# Triangle_Generator.net
KiCad netlist of a schematic drawn in Altium Designer
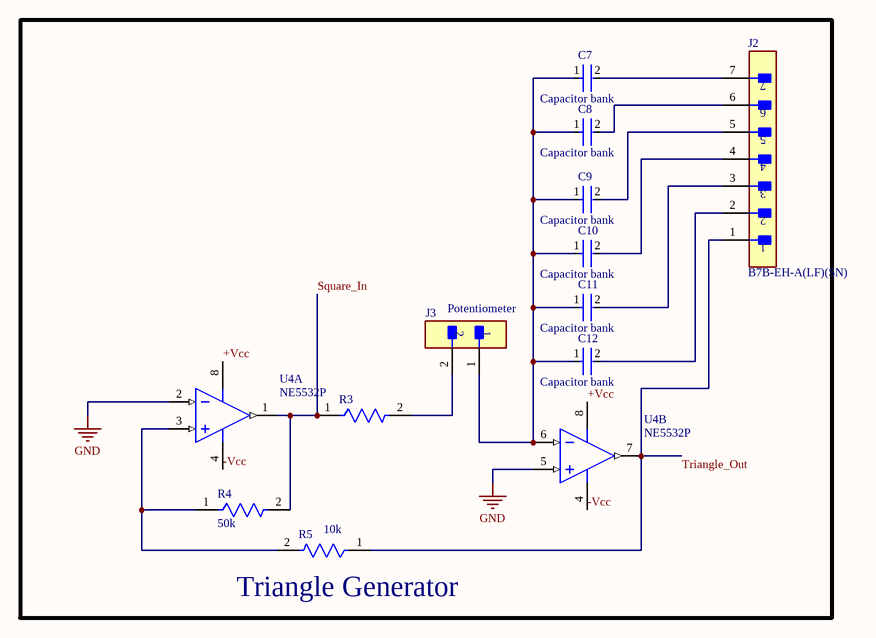
[diagram p0: Triangle_Generator.SchDoc]

(export (version "E")
  (design (tool "Eeschema 10.0.6"))
  (components
    (comp (ref "C7")
      (value "Capacitor bank")
      (footprint "FP-F471K33Y5RP6UK5R-MFG")
      (description "CAP CER 470PF 2KV Y5R RADIAL")
      (fields (field (name "TOLERANCE") "10%") (field (name "VOLTAGE") "2kV"))
      (libsource (lib "Altium Content Vault") (part "b4654b650e69147ec39a6b967a45e02"))
    )
    (comp (ref "C8")
      (value "Capacitor bank")
      (footprint "FP-F471K33Y5RP6UK5R-MFG")
      (description "CAP CER 470PF 2KV Y5R RADIAL")
      (fields (field (name "TOLERANCE") "10%") (field (name "VOLTAGE") "2kV"))
      (libsource (lib "Altium Content Vault") (part "b4654b650e69147ec39a6b967a45e02"))
    )
    (comp (ref "C9")
      (value "Capacitor bank")
      (footprint "FP-F471K33Y5RP6UK5R-MFG")
      (description "CAP CER 470PF 2KV Y5R RADIAL")
      (fields (field (name "TOLERANCE") "10%") (field (name "VOLTAGE") "2kV"))
      (libsource (lib "Altium Content Vault") (part "b4654b650e69147ec39a6b967a45e02"))
    )
    (comp (ref "C10")
      (value "Capacitor bank")
      (footprint "FP-F471K33Y5RP6UK5R-MFG")
      (description "CAP CER 470PF 2KV Y5R RADIAL")
      (fields (field (name "TOLERANCE") "10%") (field (name "VOLTAGE") "2kV"))
      (libsource (lib "Altium Content Vault") (part "b4654b650e69147ec39a6b967a45e02"))
    )
    (comp (ref "C11")
      (value "Capacitor bank")
      (footprint "FP-F471K33Y5RP6UK5R-MFG")
      (description "CAP CER 470PF 2KV Y5R RADIAL")
      (fields (field (name "TOLERANCE") "10%") (field (name "VOLTAGE") "2kV"))
      (libsource (lib "Altium Content Vault") (part "b4654b650e69147ec39a6b967a45e02"))
    )
    (comp (ref "C12")
      (value "Capacitor bank")
      (footprint "FP-F471K33Y5RP6UK5R-MFG")
      (description "CAP CER 470PF 2KV Y5R RADIAL")
      (fields (field (name "TOLERANCE") "10%") (field (name "VOLTAGE") "2kV"))
      (libsource (lib "Altium Content Vault") (part "b4654b650e69147ec39a6b967a45e02"))
    )
    (comp (ref "J2")
      (value "B7B-EH-A(LF)(SN)")
      (footprint "FP-B7B-EH-A_LF_SN-MFG")
      (description "CONN HEADER VERT 7POS 2.5MM")
      (libsource (lib "Altium Content Vault") (part "5bcee6b94e1fee4be3f4cc3a650a442"))
    )
    (comp (ref "J3")
      (value "Potentiometer")
      (footprint "FP-B2B-XH-A_LF_SN-MFG")
      (description "CONN HEADER VERT 2POS 2.5MM")
      (libsource (lib "Altium Content Vault") (part "3bc925449376181038e59eaffc5286c"))
    )
    (comp (ref "R3")
      (value "~")
      (footprint "FP-VR37-MFG")
      (description "RES 1.2M OHM 5% 1/2W AXIAL")
      (fields (field (name "TOLERANCE") "5%"))
      (libsource (lib "Altium Content Vault") (part "1029c3af85768c4190bb7ad29bc67b5"))
    )
    (comp (ref "R4")
      (value "50k")
      (footprint "FP-VR37-MFG")
      (description "RES 1.2M OHM 5% 1/2W AXIAL")
      (fields (field (name "TOLERANCE") "5%"))
      (libsource (lib "Altium Content Vault") (part "1029c3af85768c4190bb7ad29bc67b5"))
    )
    (comp (ref "R5")
      (value "10k")
      (footprint "FP-VR37-MFG")
      (description "RES 1.2M OHM 5% 1/2W AXIAL")
      (fields (field (name "TOLERANCE") "5%"))
      (libsource (lib "Altium Content Vault") (part "1029c3af85768c4190bb7ad29bc67b5"))
    )
    (comp (ref "U4")
      (value "NE5532P")
      (footprint "P0008A")
      (fields (field (name "MANUFACTURER") "Texas Instruments"))
      (libsource (lib "Altium Content Vault") (part "TI-AMP-D6-2-8_D"))
    )
  )
  (nets
    (net (code "1") (name "/+Vcc") (class "Default")
      (node (ref "U4") (pin "8") (pinfunction "VCC+_8") (pintype "power_in"))
    )
    (net (code "2") (name "/-Vcc") (class "Default")
      (node (ref "U4") (pin "4") (pinfunction "VCC-_4") (pintype "power_in"))
    )
    (net (code "3") (name "/Square_In") (class "Default")
      (node (ref "R3") (pin "1") (pinfunction "1_1") (pintype "passive"))
      (node (ref "R4") (pin "2") (pinfunction "2_2") (pintype "passive"))
      (node (ref "U4") (pin "1") (pinfunction "OUT1_1") (pintype "output"))
    )
    (net (code "4") (name "/Triangle_Out") (class "Default")
      (node (ref "J2") (pin "1") (pinfunction "1_1") (pintype "passive"))
      (node (ref "R5") (pin "1") (pinfunction "1_1") (pintype "passive"))
      (node (ref "U4") (pin "7") (pinfunction "OUT2_7") (pintype "output"))
    )
    (net (code "5") (name "GND") (class "Default")
      (node (ref "U4") (pin "2") (pinfunction "IN1-_2") (pintype "input"))
      (node (ref "U4") (pin "5") (pinfunction "IN2+_5") (pintype "input"))
    )
    (net (code "6") (name "Net-(C7-Pad2)") (class "Default")
      (node (ref "C7") (pin "2") (pinfunction "2_2") (pintype "passive"))
      (node (ref "J2") (pin "7") (pinfunction "7_7") (pintype "passive"))
    )
    (net (code "7") (name "Net-(C8-Pad2)") (class "Default")
      (node (ref "C8") (pin "2") (pinfunction "2_2") (pintype "passive"))
      (node (ref "J2") (pin "6") (pinfunction "6_6") (pintype "passive"))
    )
    (net (code "8") (name "Net-(C9-Pad2)") (class "Default")
      (node (ref "C9") (pin "2") (pinfunction "2_2") (pintype "passive"))
      (node (ref "J2") (pin "5") (pinfunction "5_5") (pintype "passive"))
    )
    (net (code "9") (name "Net-(C10-Pad2)") (class "Default")
      (node (ref "C10") (pin "2") (pinfunction "2_2") (pintype "passive"))
      (node (ref "J2") (pin "4") (pinfunction "4_4") (pintype "passive"))
    )
    (net (code "10") (name "Net-(C11-Pad2)") (class "Default")
      (node (ref "C11") (pin "2") (pinfunction "2_2") (pintype "passive"))
      (node (ref "J2") (pin "3") (pinfunction "3_3") (pintype "passive"))
    )
    (net (code "11") (name "Net-(C12-Pad2)") (class "Default")
      (node (ref "C12") (pin "2") (pinfunction "2_2") (pintype "passive"))
      (node (ref "J2") (pin "2") (pinfunction "2_2") (pintype "passive"))
    )
    (net (code "12") (name "Net-(J3-Pad2)") (class "Default")
      (node (ref "J3") (pin "2") (pinfunction "2_2") (pintype "passive"))
      (node (ref "R3") (pin "2") (pinfunction "2_2") (pintype "passive"))
    )
    (net (code "13") (name "Net-(U4A-IN1+)") (class "Default")
      (node (ref "R4") (pin "1") (pinfunction "1_1") (pintype "passive"))
      (node (ref "R5") (pin "2") (pinfunction "2_2") (pintype "passive"))
      (node (ref "U4") (pin "3") (pinfunction "IN1+_3") (pintype "input"))
    )
    (net (code "14") (name "Net-(U4B-IN2-)") (class "Default")
      (node (ref "C10") (pin "1") (pinfunction "1_1") (pintype "passive"))
      (node (ref "C11") (pin "1") (pinfunction "1_1") (pintype "passive"))
      (node (ref "C12") (pin "1") (pinfunction "1_1") (pintype "passive"))
      (node (ref "C7") (pin "1") (pinfunction "1_1") (pintype "passive"))
      (node (ref "C8") (pin "1") (pinfunction "1_1") (pintype "passive"))
      (node (ref "C9") (pin "1") (pinfunction "1_1") (pintype "passive"))
      (node (ref "J3") (pin "1") (pinfunction "1_1") (pintype "passive"))
      (node (ref "U4") (pin "6") (pinfunction "IN2-_6") (pintype "input"))
    )
  )
)
